# drive_brake.net
KiCad netlist of a schematic drawn in EAGLE
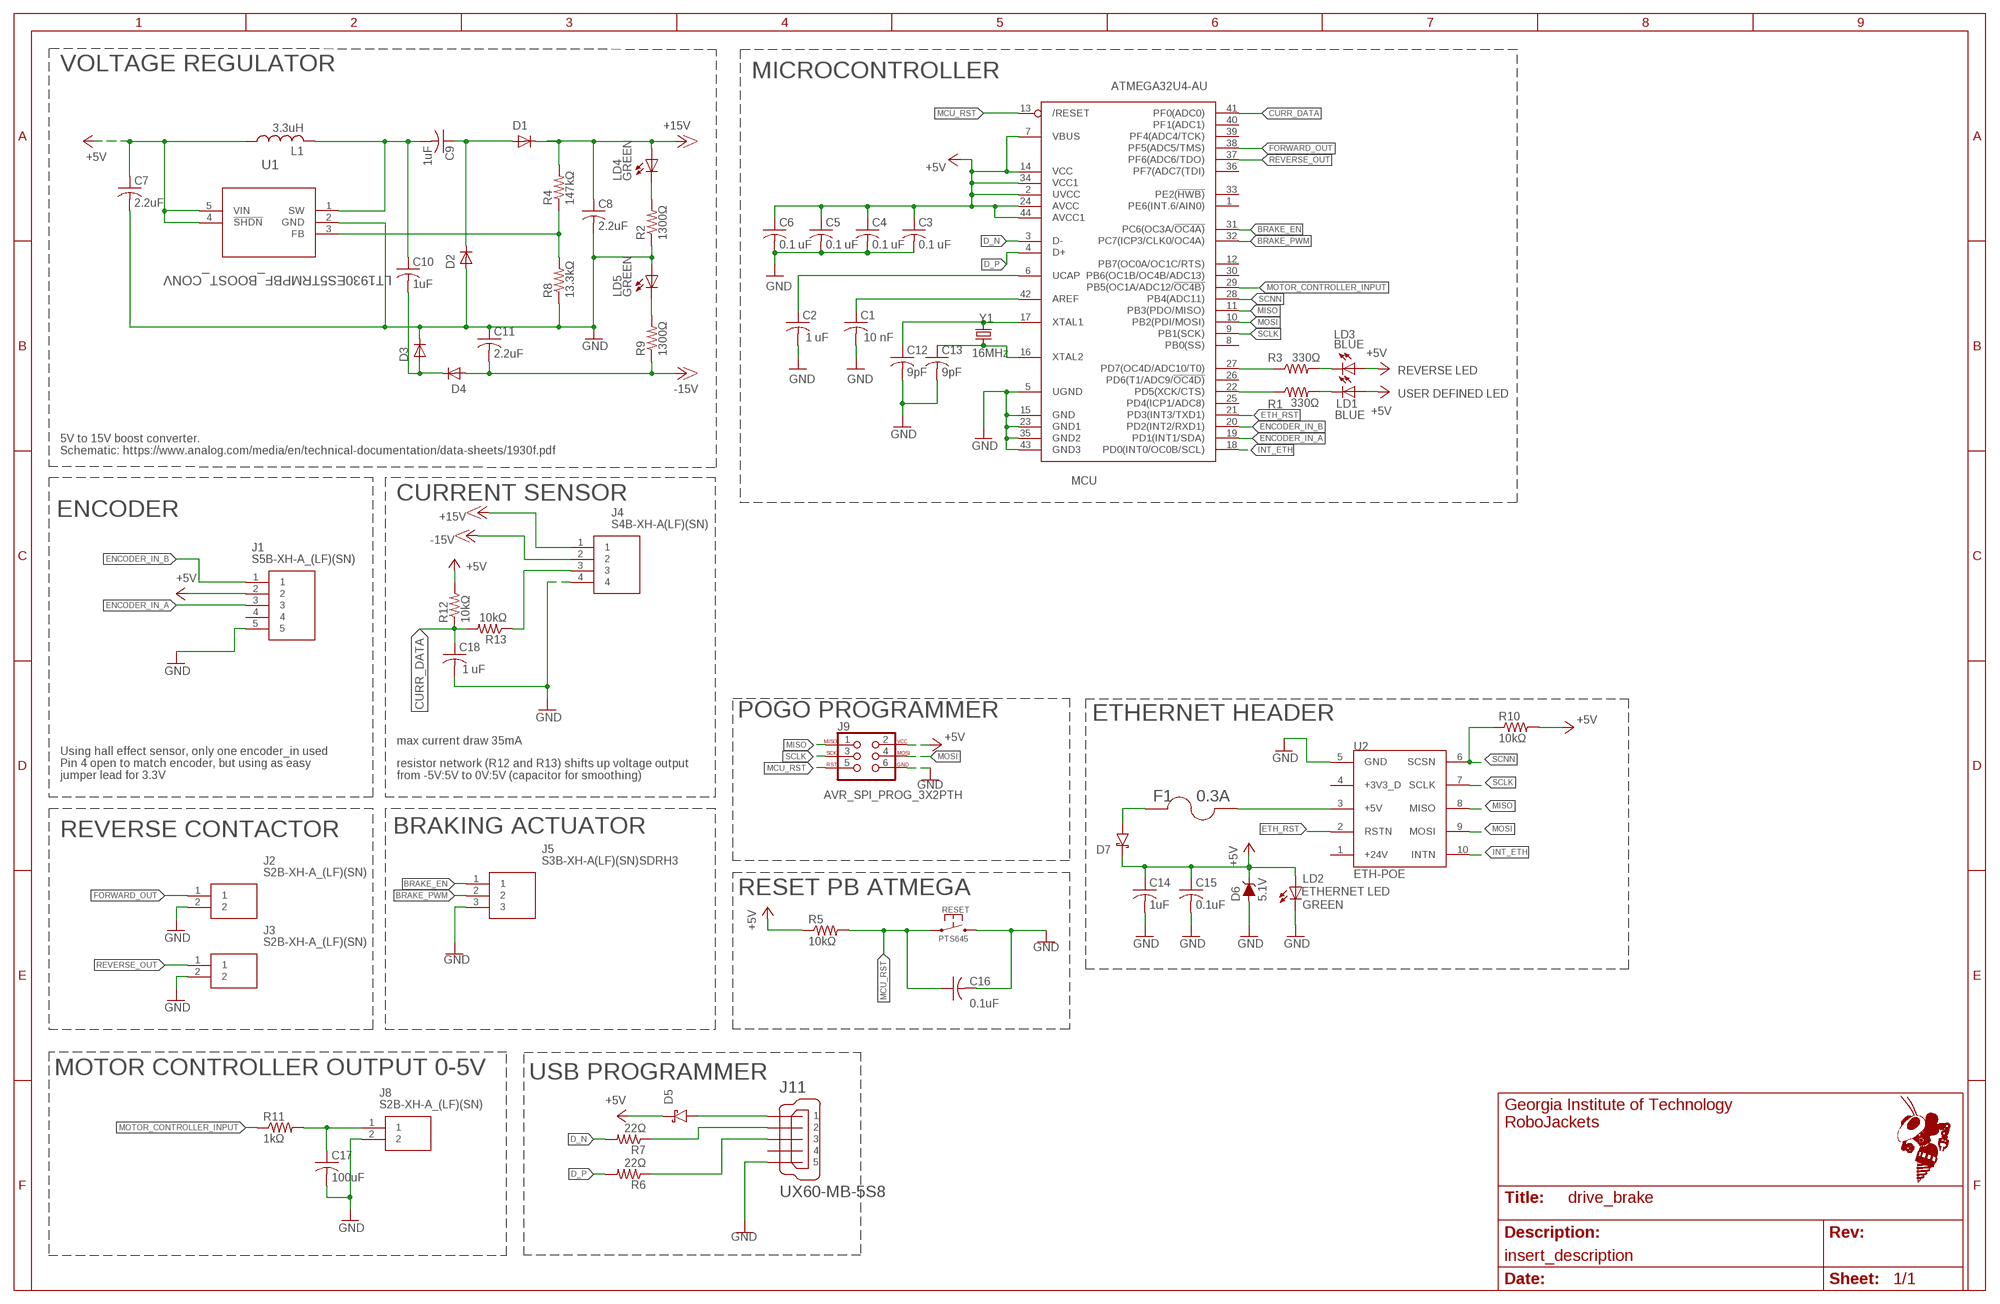
[diagram p0: schematic, sheet 1]

(export (version "E")
  (design (tool "Eeschema 10.0.6"))
  (components
    (comp (ref "C1")
      (value "10 nF")
      (footprint "eagle-import:C0603")
      (libsource (lib "eagle-import") (part "C-USC0603"))
    )
    (comp (ref "C2")
      (value "1 uF")
      (footprint "eagle-import:C0603")
      (libsource (lib "eagle-import") (part "C-USC0603"))
    )
    (comp (ref "C3")
      (value "0.1 uF")
      (footprint "eagle-import:C0603")
      (libsource (lib "eagle-import") (part "C-USC0603"))
    )
    (comp (ref "C4")
      (value "0.1 uF")
      (footprint "eagle-import:C0603")
      (libsource (lib "eagle-import") (part "C-USC0603"))
    )
    (comp (ref "C5")
      (value "0.1 uF")
      (footprint "eagle-import:C0603")
      (libsource (lib "eagle-import") (part "C-USC0603"))
    )
    (comp (ref "C6")
      (value "0.1 uF")
      (footprint "eagle-import:C0603")
      (libsource (lib "eagle-import") (part "C-USC0603"))
    )
    (comp (ref "C7")
      (value "2.2uF")
      (footprint "eagle-import:C0805")
      (libsource (lib "eagle-import") (part "C-USC0805"))
    )
    (comp (ref "C8")
      (value "2.2uF")
      (footprint "eagle-import:C1206")
      (libsource (lib "eagle-import") (part "C-USC1206"))
    )
    (comp (ref "C9")
      (value "1uF")
      (footprint "eagle-import:C0603")
      (libsource (lib "eagle-import") (part "C-USC0603"))
    )
    (comp (ref "C10")
      (value "1uF")
      (footprint "eagle-import:C0603")
      (libsource (lib "eagle-import") (part "C-USC0603"))
    )
    (comp (ref "C11")
      (value "2.2uF")
      (footprint "eagle-import:C1206")
      (libsource (lib "eagle-import") (part "C-USC1206"))
    )
    (comp (ref "C12")
      (value "9pF")
      (footprint "eagle-import:C0603")
      (libsource (lib "eagle-import") (part "C-USC0603"))
    )
    (comp (ref "C13")
      (value "9pF")
      (footprint "eagle-import:C0603")
      (libsource (lib "eagle-import") (part "C-USC0603"))
    )
    (comp (ref "C14")
      (value "1uF")
      (footprint "eagle-import:C0603")
      (libsource (lib "eagle-import") (part "C-USC0603"))
    )
    (comp (ref "C15")
      (value "0.1uF")
      (footprint "eagle-import:C0603")
      (libsource (lib "eagle-import") (part "C-USC0603"))
    )
    (comp (ref "C16")
      (value "0.1uF")
      (footprint "eagle-import:C0603")
      (libsource (lib "eagle-import") (part "C-USC0603"))
    )
    (comp (ref "C17")
      (value "100uF")
      (footprint "eagle-import:C1206")
      (libsource (lib "eagle-import") (part "C-USC1206"))
    )
    (comp (ref "C18")
      (value "1 uF")
      (footprint "eagle-import:C0603")
      (libsource (lib "eagle-import") (part "C-USC0603"))
    )
    (comp (ref "D1")
      (value "DIODE-SOD123")
      (footprint "eagle-import:SOD123")
      (libsource (lib "eagle-import") (part "DIODE-SOD123"))
    )
    (comp (ref "D2")
      (value "DIODE-SOD123")
      (footprint "eagle-import:SOD123")
      (libsource (lib "eagle-import") (part "DIODE-SOD123"))
    )
    (comp (ref "D3")
      (value "DIODE-SOD123")
      (footprint "eagle-import:SOD123")
      (libsource (lib "eagle-import") (part "DIODE-SOD123"))
    )
    (comp (ref "D4")
      (value "DIODE-SOD123")
      (footprint "eagle-import:SOD123")
      (libsource (lib "eagle-import") (part "DIODE-SOD123"))
    )
    (comp (ref "D5")
      (value "SCHOTTKYSOD-323")
      (footprint "eagle-import:SOD-323")
      (libsource (lib "eagle-import") (part "SCHOTTKYSOD-323"))
    )
    (comp (ref "D6")
      (value "5.1V")
      (footprint "eagle-import:SOD-323")
      (libsource (lib "eagle-import") (part "DIODE-ZENER-MM3Z3V3T1G"))
    )
    (comp (ref "D7")
      (value "SCHOTTKYSOD-323")
      (footprint "eagle-import:SOD-323")
      (libsource (lib "eagle-import") (part "SCHOTTKYSOD-323"))
    )
    (comp (ref "F1")
      (value "0.3A")
      (footprint "eagle-import:F1206")
      (libsource (lib "eagle-import") (part "FUSE1206"))
    )
    (comp (ref "J1")
      (value "S5B-XH-A_(LF)(SN)")
      (footprint "eagle-import:SHDR5W80P0X250_1X5_1490X1150X6")
      (fields
        (field (name "MANUFACTURER_PART_NUMBER") "S5B-XH-A (LF)(SN)")
        (field (name "RS_PART_NUMBER") "5469072")
      )
      (libsource (lib "eagle-import") (part "S5B-XH-A_(LF)(SN)"))
    )
    (comp (ref "J2")
      (value "S2B-XH-A_(LF)(SN)")
      (footprint "eagle-import:SHDR2W80P0X250_1X2_740X1150X61")
      (fields (field (name "MANUFACTURER_PART_NUMBER") "S2B-XH-A (LF)(SN)"))
      (libsource (lib "eagle-import") (part "S2B-XH-A_(LF)(SN)"))
    )
    (comp (ref "J3")
      (value "S2B-XH-A_(LF)(SN)")
      (footprint "eagle-import:SHDR2W80P0X250_1X2_740X1150X61")
      (fields (field (name "MANUFACTURER_PART_NUMBER") "S2B-XH-A (LF)(SN)"))
      (libsource (lib "eagle-import") (part "S2B-XH-A_(LF)(SN)"))
    )
    (comp (ref "J4")
      (value "S4B-XH-A(LF)(SN)")
      (footprint "eagle-import:SHDR4W64P0X250_1X4_1240X1155X7")
      (fields (field (name "RS_PART_NUMBER") "8201589P"))
      (libsource (lib "eagle-import") (part "S4B-XH-A(LF)(SN)"))
    )
    (comp (ref "J5")
      (value "S3B-XH-A(LF)(SN)SDRH3")
      (footprint "eagle-import:SHDR4")
      (libsource (lib "eagle-import") (part "S3B-XH-A(LF)(SN)SDRH3"))
    )
    (comp (ref "J8")
      (value "S2B-XH-A_(LF)(SN)")
      (footprint "eagle-import:SHDR2W80P0X250_1X2_740X1150X61")
      (fields (field (name "MANUFACTURER_PART_NUMBER") "S2B-XH-A (LF)(SN)"))
      (libsource (lib "eagle-import") (part "S2B-XH-A_(LF)(SN)"))
    )
    (comp (ref "J9")
      (value "AVR_SPI_PROG_3X2PTH")
      (footprint "eagle-import:2X3")
      (libsource (lib "eagle-import") (part "AVR_SPI_PROG_3X2PTH"))
    )
    (comp (ref "J11")
      (value "UX60-MB-5S8")
      (footprint "eagle-import:UX60-MB-5S8")
      (libsource (lib "eagle-import") (part "UX60-MB-5S?8"))
    )
    (comp (ref "L1")
      (value "3.3uH")
      (footprint "eagle-import:L3225M")
      (libsource (lib "eagle-import") (part "L-USL3225M"))
    )
    (comp (ref "LD1")
      (value "BLUE")
      (footprint "eagle-import:LED-0603")
      (libsource (lib "eagle-import") (part "LED0603"))
    )
    (comp (ref "LD2")
      (value "GREEN")
      (footprint "eagle-import:LED-0603")
      (libsource (lib "eagle-import") (part "LED0603"))
    )
    (comp (ref "LD3")
      (value "BLUE")
      (footprint "eagle-import:LED-0603")
      (libsource (lib "eagle-import") (part "LED0603"))
    )
    (comp (ref "LD4")
      (value "GREEN")
      (footprint "eagle-import:LED-0603")
      (libsource (lib "eagle-import") (part "LED0603"))
    )
    (comp (ref "LD5")
      (value "GREEN")
      (footprint "eagle-import:LED-0603")
      (libsource (lib "eagle-import") (part "LED0603"))
    )
    (comp (ref "MCU")
      (value "ATMEGA32U4-AU")
      (footprint "eagle-import:TQFP44")
      (libsource (lib "eagle-import") (part "ATMEGA32U4-AU"))
    )
    (comp (ref "R1")
      (value "330Ω")
      (footprint "eagle-import:0603-RES")
      (libsource (lib "eagle-import") (part "RESISTOR0603-RES"))
    )
    (comp (ref "R2")
      (value "1300Ω")
      (footprint "eagle-import:R0603")
      (libsource (lib "eagle-import") (part "R-US_R0603"))
    )
    (comp (ref "R3")
      (value "330Ω")
      (footprint "eagle-import:0603-RES")
      (libsource (lib "eagle-import") (part "RESISTOR0603-RES"))
    )
    (comp (ref "R4")
      (value "147kΩ")
      (footprint "eagle-import:R0603")
      (libsource (lib "eagle-import") (part "R-US_R0603"))
    )
    (comp (ref "R5")
      (value "10kΩ")
      (footprint "eagle-import:R0603")
      (libsource (lib "eagle-import") (part "R-US_R0603"))
    )
    (comp (ref "R6")
      (value "22Ω")
      (footprint "eagle-import:0603-RES")
      (libsource (lib "eagle-import") (part "RESISTOR0603-RES"))
    )
    (comp (ref "R7")
      (value "22Ω")
      (footprint "eagle-import:0603-RES")
      (libsource (lib "eagle-import") (part "RESISTOR0603-RES"))
    )
    (comp (ref "R8")
      (value "13.3kΩ")
      (footprint "eagle-import:R0603")
      (libsource (lib "eagle-import") (part "R-US_R0603"))
    )
    (comp (ref "R9")
      (value "1300Ω")
      (footprint "eagle-import:R0603")
      (libsource (lib "eagle-import") (part "R-US_R0603"))
    )
    (comp (ref "R10")
      (value "10kΩ")
      (footprint "eagle-import:R0603")
      (libsource (lib "eagle-import") (part "R-US_R0603"))
    )
    (comp (ref "R11")
      (value "1kΩ")
      (footprint "eagle-import:0603-RES")
      (libsource (lib "eagle-import") (part "RESISTOR0603-RES"))
    )
    (comp (ref "R12")
      (value "10kΩ")
      (footprint "eagle-import:0603-RES")
      (libsource (lib "eagle-import") (part "RESISTOR0603-RES"))
    )
    (comp (ref "R13")
      (value "10kΩ")
      (footprint "eagle-import:0603-RES")
      (libsource (lib "eagle-import") (part "RESISTOR0603-RES"))
    )
    (comp (ref "RESET")
      (value "PTS645")
      (footprint "eagle-import:PTS645")
      (libsource (lib "eagle-import") (part "PTS645"))
    )
    (comp (ref "U1")
      (value "LT1930ES5TRMPBF_BOOST_CONV")
      (footprint "eagle-import:SOT-5_S")
      (fields (field (name "MANUFACTURER_PART_NUMBER") "LT1930ES5#TRMPBF"))
      (libsource (lib "eagle-import") (part "LT1930ES5TRMPBF_BOOST_CONV"))
    )
    (comp (ref "U2")
      (value "ETH-POE")
      (footprint "eagle-import:HDRVR10W64P4000X254_2X5_1016X508X254B")
      (libsource (lib "eagle-import") (part "ETH-POE"))
    )
    (comp (ref "Y1")
      (value "16MHz")
      (footprint "eagle-import:CRYSTAL-SMD-5X3")
      (libsource (lib "eagle-import") (part "CRYSTAL5X3"))
    )
  )
  (nets
    (net (code "1") (name "+5V") (class "Default")
      (node (ref "C14") (pin "1") (pinfunction "1_1") (pintype "passive"))
      (node (ref "C15") (pin "1") (pinfunction "1_1") (pintype "passive"))
      (node (ref "C3") (pin "1") (pinfunction "1_1") (pintype "passive"))
      (node (ref "C4") (pin "1") (pinfunction "1_1") (pintype "passive"))
      (node (ref "C5") (pin "1") (pinfunction "1_1") (pintype "passive"))
      (node (ref "C6") (pin "1") (pinfunction "1_1") (pintype "passive"))
      (node (ref "C7") (pin "1") (pinfunction "1_1") (pintype "passive"))
      (node (ref "D5") (pin "C") (pinfunction "C_C") (pintype "passive"))
      (node (ref "D6") (pin "C") (pinfunction "C_C") (pintype "passive"))
      (node (ref "D7") (pin "C") (pinfunction "C_C") (pintype "passive"))
      (node (ref "J1") (pin "2") (pinfunction "2_2") (pintype "bidirectional"))
      (node (ref "J9") (pin "2") (pinfunction "2_2") (pintype "passive"))
      (node (ref "L1") (pin "1") (pinfunction "1_1") (pintype "passive"))
      (node (ref "LD1") (pin "A") (pinfunction "A_A") (pintype "passive"))
      (node (ref "LD2") (pin "A") (pinfunction "A_A") (pintype "passive"))
      (node (ref "LD3") (pin "A") (pinfunction "A_A") (pintype "passive"))
      (node (ref "MCU") (pin "14") (pinfunction "VCC_14") (pintype "bidirectional"))
      (node (ref "MCU") (pin "2") (pinfunction "UVCC_2") (pintype "bidirectional"))
      (node (ref "MCU") (pin "24") (pinfunction "AVCC_24") (pintype "bidirectional"))
      (node (ref "MCU") (pin "34") (pinfunction "VCC1_34") (pintype "bidirectional"))
      (node (ref "MCU") (pin "44") (pinfunction "AVCC1_44") (pintype "bidirectional"))
      (node (ref "MCU") (pin "7") (pinfunction "VBUS_7") (pintype "bidirectional"))
      (node (ref "R10") (pin "2") (pinfunction "2_2") (pintype "passive"))
      (node (ref "R12") (pin "2") (pinfunction "2_2") (pintype "passive"))
      (node (ref "R5") (pin "1") (pinfunction "1_1") (pintype "passive"))
      (node (ref "U1") (pin "4") (pinfunction "~{SHDN}_4") (pintype "input"))
      (node (ref "U1") (pin "5") (pinfunction "VIN_5") (pintype "power_in"))
    )
    (net (code "2") (name "+15V") (class "Default")
      (node (ref "C8") (pin "1") (pinfunction "1_1") (pintype "passive"))
      (node (ref "D1") (pin "C") (pinfunction "C_C") (pintype "passive"))
      (node (ref "J4") (pin "1") (pinfunction "1_1") (pintype "bidirectional"))
      (node (ref "LD4") (pin "A") (pinfunction "A_A") (pintype "passive"))
      (node (ref "R4") (pin "2") (pinfunction "2_2") (pintype "passive"))
    )
    (net (code "3") (name "-15V") (class "Default")
      (node (ref "C11") (pin "2") (pinfunction "2_2") (pintype "passive"))
      (node (ref "D4") (pin "A") (pinfunction "A_A") (pintype "passive"))
      (node (ref "J4") (pin "2") (pinfunction "2_2") (pintype "bidirectional"))
      (node (ref "R9") (pin "1") (pinfunction "1_1") (pintype "passive"))
    )
    (net (code "4") (name "BRAKE_EN") (class "Default")
      (node (ref "J5") (pin "1") (pinfunction "1_1") (pintype "bidirectional"))
      (node (ref "MCU") (pin "31") (pinfunction "PC6(OC3A/~{OC4A})_31") (pintype "bidirectional"))
    )
    (net (code "5") (name "BRAKE_PWM") (class "Default")
      (node (ref "J5") (pin "2") (pinfunction "2_2") (pintype "bidirectional"))
      (node (ref "MCU") (pin "32") (pinfunction "PC7(ICP3/CLK0/OC4A)_32") (pintype "bidirectional"))
    )
    (net (code "6") (name "CURR_DATA") (class "Default")
      (node (ref "C18") (pin "1") (pinfunction "1_1") (pintype "passive"))
      (node (ref "MCU") (pin "41") (pinfunction "PF0(ADC0)_41") (pintype "bidirectional"))
      (node (ref "R12") (pin "1") (pinfunction "1_1") (pintype "passive"))
      (node (ref "R13") (pin "2") (pinfunction "2_2") (pintype "passive"))
    )
    (net (code "7") (name "D_N") (class "Default")
      (node (ref "MCU") (pin "3") (pinfunction "D-_3") (pintype "bidirectional"))
      (node (ref "R7") (pin "2") (pinfunction "2_2") (pintype "passive"))
    )
    (net (code "8") (name "D_P") (class "Default")
      (node (ref "MCU") (pin "4") (pinfunction "D+_4") (pintype "bidirectional"))
      (node (ref "R6") (pin "2") (pinfunction "2_2") (pintype "passive"))
    )
    (net (code "9") (name "ENCODER_IN_A") (class "Default")
      (node (ref "J1") (pin "3") (pinfunction "3_3") (pintype "bidirectional"))
      (node (ref "MCU") (pin "19") (pinfunction "PD1(INT1/SDA)_19") (pintype "bidirectional"))
    )
    (net (code "10") (name "ENCODER_IN_B") (class "Default")
      (node (ref "J1") (pin "1") (pinfunction "1_1") (pintype "bidirectional"))
      (node (ref "MCU") (pin "20") (pinfunction "PD2(INT2/RXD1)_20") (pintype "bidirectional"))
    )
    (net (code "11") (name "ETH_RST") (class "Default")
      (node (ref "MCU") (pin "21") (pinfunction "PD3(INT3/TXD1)_21") (pintype "bidirectional"))
      (node (ref "U2") (pin "2") (pinfunction "RSTN_2") (pintype "bidirectional"))
    )
    (net (code "12") (name "FORWARD_OUT") (class "Default")
      (node (ref "J2") (pin "1") (pinfunction "1_1") (pintype "bidirectional"))
      (node (ref "MCU") (pin "38") (pinfunction "PF5(ADC5/TMS)_38") (pintype "bidirectional"))
    )
    (net (code "13") (name "GND") (class "Default")
      (node (ref "C1") (pin "2") (pinfunction "2_2") (pintype "passive"))
      (node (ref "C11") (pin "1") (pinfunction "1_1") (pintype "passive"))
      (node (ref "C12") (pin "2") (pinfunction "2_2") (pintype "passive"))
      (node (ref "C13") (pin "2") (pinfunction "2_2") (pintype "passive"))
      (node (ref "C14") (pin "2") (pinfunction "2_2") (pintype "passive"))
      (node (ref "C15") (pin "2") (pinfunction "2_2") (pintype "passive"))
      (node (ref "C16") (pin "2") (pinfunction "2_2") (pintype "passive"))
      (node (ref "C17") (pin "2") (pinfunction "2_2") (pintype "passive"))
      (node (ref "C18") (pin "2") (pinfunction "2_2") (pintype "passive"))
      (node (ref "C2") (pin "2") (pinfunction "2_2") (pintype "passive"))
      (node (ref "C3") (pin "2") (pinfunction "2_2") (pintype "passive"))
      (node (ref "C4") (pin "2") (pinfunction "2_2") (pintype "passive"))
      (node (ref "C5") (pin "2") (pinfunction "2_2") (pintype "passive"))
      (node (ref "C6") (pin "2") (pinfunction "2_2") (pintype "passive"))
      (node (ref "C7") (pin "2") (pinfunction "2_2") (pintype "passive"))
      (node (ref "C8") (pin "2") (pinfunction "2_2") (pintype "passive"))
      (node (ref "D2") (pin "A") (pinfunction "A_A") (pintype "passive"))
      (node (ref "D3") (pin "C") (pinfunction "C_C") (pintype "passive"))
      (node (ref "D6") (pin "A") (pinfunction "A_A") (pintype "passive"))
      (node (ref "J1") (pin "5") (pinfunction "5_5") (pintype "bidirectional"))
      (node (ref "J11") (pin "5") (pinfunction "5_5") (pintype "passive"))
      (node (ref "J2") (pin "2") (pinfunction "2_2") (pintype "bidirectional"))
      (node (ref "J3") (pin "2") (pinfunction "2_2") (pintype "bidirectional"))
      (node (ref "J4") (pin "4") (pinfunction "4_4") (pintype "bidirectional"))
      (node (ref "J5") (pin "3") (pinfunction "3_3") (pintype "bidirectional"))
      (node (ref "J8") (pin "2") (pinfunction "2_2") (pintype "bidirectional"))
      (node (ref "J9") (pin "6") (pinfunction "6_6") (pintype "passive"))
      (node (ref "LD2") (pin "C") (pinfunction "C_C") (pintype "passive"))
      (node (ref "LD5") (pin "A") (pinfunction "A_A") (pintype "passive"))
      (node (ref "MCU") (pin "15") (pinfunction "GND_15") (pintype "bidirectional"))
      (node (ref "MCU") (pin "23") (pinfunction "GND1_23") (pintype "bidirectional"))
      (node (ref "MCU") (pin "35") (pinfunction "GND2_35") (pintype "bidirectional"))
      (node (ref "MCU") (pin "43") (pinfunction "GND3_43") (pintype "bidirectional"))
      (node (ref "MCU") (pin "5") (pinfunction "UGND_5") (pintype "bidirectional"))
      (node (ref "R2") (pin "1") (pinfunction "1_1") (pintype "passive"))
      (node (ref "R8") (pin "1") (pinfunction "1_1") (pintype "passive"))
      (node (ref "RESET") (pin "P$3") (pinfunction "2_P$3") (pintype "passive"))
      (node (ref "RESET") (pin "P$4") (pinfunction "2_P$4") (pintype "passive"))
      (node (ref "U1") (pin "2") (pinfunction "GND_2") (pintype "power_in"))
      (node (ref "U2") (pin "5") (pinfunction "GND_5") (pintype "bidirectional"))
    )
    (net (code "14") (name "INT_ETH") (class "Default")
      (node (ref "MCU") (pin "18") (pinfunction "PD0(INT0/OC0B/SCL)_18") (pintype "bidirectional"))
      (node (ref "U2") (pin "10") (pinfunction "INTN_10") (pintype "bidirectional"))
    )
    (net (code "15") (name "MCU_RST") (class "Default")
      (node (ref "C16") (pin "1") (pinfunction "1_1") (pintype "passive"))
      (node (ref "J9") (pin "5") (pinfunction "5_5") (pintype "passive"))
      (node (ref "MCU") (pin "13") (pinfunction "/RESET_13") (pintype "bidirectional"))
      (node (ref "R5") (pin "2") (pinfunction "2_2") (pintype "passive"))
      (node (ref "RESET") (pin "P$1") (pinfunction "1_P$1") (pintype "passive"))
      (node (ref "RESET") (pin "P$2") (pinfunction "1_P$2") (pintype "passive"))
    )
    (net (code "16") (name "MISO") (class "Default")
      (node (ref "J9") (pin "1") (pinfunction "1_1") (pintype "passive"))
      (node (ref "MCU") (pin "11") (pinfunction "PB3(PDO/MISO)_11") (pintype "bidirectional"))
      (node (ref "U2") (pin "8") (pinfunction "MISO_8") (pintype "bidirectional"))
    )
    (net (code "17") (name "MOSI") (class "Default")
      (node (ref "J9") (pin "4") (pinfunction "4_4") (pintype "passive"))
      (node (ref "MCU") (pin "10") (pinfunction "PB2(PDI/MOSI)_10") (pintype "bidirectional"))
      (node (ref "U2") (pin "9") (pinfunction "MOSI_9") (pintype "bidirectional"))
    )
    (net (code "18") (name "MOTOR_CONTROLLER_INPUT") (class "Default")
      (node (ref "MCU") (pin "29") (pinfunction "PB5(OC1A/ADC12/~{OC4B})_29") (pintype "bidirectional"))
      (node (ref "R11") (pin "1") (pinfunction "1_1") (pintype "passive"))
    )
    (net (code "19") (name "Net-(C9-Pad1)") (class "Default")
      (node (ref "C9") (pin "1") (pinfunction "1_1") (pintype "passive"))
      (node (ref "D1") (pin "A") (pinfunction "A_A") (pintype "passive"))
      (node (ref "D2") (pin "C") (pinfunction "C_C") (pintype "passive"))
    )
    (net (code "20") (name "Net-(C10-Pad2)") (class "Default")
      (node (ref "C10") (pin "2") (pinfunction "2_2") (pintype "passive"))
      (node (ref "D3") (pin "A") (pinfunction "A_A") (pintype "passive"))
      (node (ref "D4") (pin "C") (pinfunction "C_C") (pintype "passive"))
    )
    (net (code "21") (name "Net-(C17-Pad1)") (class "Default")
      (node (ref "C17") (pin "1") (pinfunction "1_1") (pintype "passive"))
      (node (ref "J8") (pin "1") (pinfunction "1_1") (pintype "bidirectional"))
      (node (ref "R11") (pin "2") (pinfunction "2_2") (pintype "passive"))
    )
    (net (code "22") (name "Net-(D5-PadA)") (class "Default")
      (node (ref "D5") (pin "A") (pinfunction "A_A") (pintype "passive"))
      (node (ref "J11") (pin "1") (pinfunction "1_1") (pintype "passive"))
    )
    (net (code "23") (name "Net-(D7-PadA)") (class "Default")
      (node (ref "D7") (pin "A") (pinfunction "A_A") (pintype "passive"))
      (node (ref "F1") (pin "1") (pinfunction "1_1") (pintype "passive"))
    )
    (net (code "24") (name "Net-(J4-Pad3)") (class "Default")
      (node (ref "J4") (pin "3") (pinfunction "3_3") (pintype "bidirectional"))
      (node (ref "R13") (pin "1") (pinfunction "1_1") (pintype "passive"))
    )
    (net (code "25") (name "Net-(J11-Pad2)") (class "Default")
      (node (ref "J11") (pin "2") (pinfunction "2_2") (pintype "passive"))
      (node (ref "R7") (pin "1") (pinfunction "1_1") (pintype "passive"))
    )
    (net (code "26") (name "Net-(J11-Pad3)") (class "Default")
      (node (ref "J11") (pin "3") (pinfunction "3_3") (pintype "passive"))
      (node (ref "R6") (pin "1") (pinfunction "1_1") (pintype "passive"))
    )
    (net (code "27") (name "Net-(LD1-PadC)") (class "Default")
      (node (ref "LD1") (pin "C") (pinfunction "C_C") (pintype "passive"))
      (node (ref "R1") (pin "2") (pinfunction "2_2") (pintype "passive"))
    )
    (net (code "28") (name "Net-(LD3-PadC)") (class "Default")
      (node (ref "LD3") (pin "C") (pinfunction "C_C") (pintype "passive"))
      (node (ref "R3") (pin "2") (pinfunction "2_2") (pintype "passive"))
    )
    (net (code "29") (name "Net-(LD4-PadC)") (class "Default")
      (node (ref "LD4") (pin "C") (pinfunction "C_C") (pintype "passive"))
      (node (ref "R2") (pin "2") (pinfunction "2_2") (pintype "passive"))
    )
    (net (code "30") (name "Net-(LD5-PadC)") (class "Default")
      (node (ref "LD5") (pin "C") (pinfunction "C_C") (pintype "passive"))
      (node (ref "R9") (pin "2") (pinfunction "2_2") (pintype "passive"))
    )
    (net (code "31") (name "Net-(MCU-AREF)") (class "Default")
      (node (ref "C1") (pin "1") (pinfunction "1_1") (pintype "passive"))
      (node (ref "MCU") (pin "42") (pinfunction "AREF_42") (pintype "bidirectional"))
    )
    (net (code "32") (name "Net-(MCU-PD5(XCK{slash}CTS))") (class "Default")
      (node (ref "MCU") (pin "22") (pinfunction "PD5(XCK/CTS)_22") (pintype "bidirectional"))
      (node (ref "R1") (pin "1") (pinfunction "1_1") (pintype "passive"))
    )
    (net (code "33") (name "Net-(MCU-PD7(OC4D{slash}ADC10{slash}T0))") (class "Default")
      (node (ref "MCU") (pin "27") (pinfunction "PD7(OC4D/ADC10/T0)_27") (pintype "bidirectional"))
      (node (ref "R3") (pin "1") (pinfunction "1_1") (pintype "passive"))
    )
    (net (code "34") (name "Net-(MCU-UCAP)") (class "Default")
      (node (ref "C2") (pin "1") (pinfunction "1_1") (pintype "passive"))
      (node (ref "MCU") (pin "6") (pinfunction "UCAP_6") (pintype "bidirectional"))
    )
    (net (code "35") (name "Net-(MCU-XTAL1)") (class "Default")
      (node (ref "C12") (pin "1") (pinfunction "1_1") (pintype "passive"))
      (node (ref "MCU") (pin "17") (pinfunction "XTAL1_17") (pintype "bidirectional"))
      (node (ref "Y1") (pin "3") (pinfunction "2_3") (pintype "passive"))
    )
    (net (code "36") (name "Net-(MCU-XTAL2)") (class "Default")
      (node (ref "C13") (pin "1") (pinfunction "1_1") (pintype "passive"))
      (node (ref "MCU") (pin "16") (pinfunction "XTAL2_16") (pintype "bidirectional"))
      (node (ref "Y1") (pin "1") (pinfunction "1_1") (pintype "passive"))
    )
    (net (code "37") (name "Net-(U1-FB)") (class "Default")
      (node (ref "R4") (pin "1") (pinfunction "1_1") (pintype "passive"))
      (node (ref "R8") (pin "2") (pinfunction "2_2") (pintype "passive"))
      (node (ref "U1") (pin "3") (pinfunction "FB_3") (pintype "input"))
    )
    (net (code "38") (name "Net-(U1-SW)") (class "Default")
      (node (ref "C10") (pin "1") (pinfunction "1_1") (pintype "passive"))
      (node (ref "C9") (pin "2") (pinfunction "2_2") (pintype "passive"))
      (node (ref "L1") (pin "2") (pinfunction "2_2") (pintype "passive"))
      (node (ref "U1") (pin "1") (pinfunction "SW_1") (pintype "passive"))
    )
    (net (code "39") (name "Net-(U2-+5V)") (class "Default")
      (node (ref "F1") (pin "2") (pinfunction "2_2") (pintype "passive"))
      (node (ref "U2") (pin "3") (pinfunction "+5V_3") (pintype "bidirectional"))
    )
    (net (code "40") (name "REVERSE_OUT") (class "Default")
      (node (ref "J3") (pin "1") (pinfunction "1_1") (pintype "bidirectional"))
      (node (ref "MCU") (pin "37") (pinfunction "PF6(ADC6/TDO)_37") (pintype "bidirectional"))
    )
    (net (code "41") (name "SCLK") (class "Default")
      (node (ref "J9") (pin "3") (pinfunction "3_3") (pintype "passive"))
      (node (ref "MCU") (pin "9") (pinfunction "PB1(SCK)_9") (pintype "bidirectional"))
      (node (ref "U2") (pin "7") (pinfunction "SCLK_7") (pintype "bidirectional"))
    )
    (net (code "42") (name "SCNN") (class "Default")
      (node (ref "MCU") (pin "28") (pinfunction "PB4(ADC11)_28") (pintype "bidirectional"))
      (node (ref "R10") (pin "1") (pinfunction "1_1") (pintype "passive"))
      (node (ref "U2") (pin "6") (pinfunction "SCSN_6") (pintype "bidirectional"))
    )
    (net (code "43") (name "unconnected-(J1-Pad4)") (class "Default")
      (node (ref "J1") (pin "4") (pinfunction "4_4") (pintype "bidirectional"))
    )
    (net (code "44") (name "unconnected-(J11-Pad4)") (class "Default")
      (node (ref "J11") (pin "4") (pinfunction "4_4") (pintype "passive"))
    )
    (net (code "45") (name "unconnected-(MCU-PB0(SS)-Pad8)") (class "Default")
      (node (ref "MCU") (pin "8") (pinfunction "PB0(SS)_8") (pintype "bidirectional"))
    )
    (net (code "46") (name "unconnected-(MCU-PB6(OC1B{slash}OC4B{slash}ADC13)-Pad30)") (class "Default")
      (node (ref "MCU") (pin "30") (pinfunction "PB6(OC1B/OC4B/ADC13)_30") (pintype "bidirectional"))
    )
    (net (code "47") (name "unconnected-(MCU-PB7(OC0A{slash}OC1C{slash}RTS)-Pad12)") (class "Default")
      (node (ref "MCU") (pin "12") (pinfunction "PB7(OC0A/OC1C/RTS)_12") (pintype "bidirectional"))
    )
    (net (code "48") (name "unconnected-(MCU-PD4(ICP1{slash}ADC8)-Pad25)") (class "Default")
      (node (ref "MCU") (pin "25") (pinfunction "PD4(ICP1/ADC8)_25") (pintype "bidirectional"))
    )
    (net (code "49") (name "unconnected-(MCU-PD6(T1{slash}ADC9{slash}~{OC4D})-Pad26)") (class "Default")
      (node (ref "MCU") (pin "26") (pinfunction "PD6(T1/ADC9/~{OC4D})_26") (pintype "bidirectional"))
    )
    (net (code "50") (name "unconnected-(MCU-PE2(~{HWB})-Pad33)") (class "Default")
      (node (ref "MCU") (pin "33") (pinfunction "PE2(~{HWB})_33") (pintype "bidirectional"))
    )
    (net (code "51") (name "unconnected-(MCU-PE6(INT.6{slash}AIN0)-Pad1)") (class "Default")
      (node (ref "MCU") (pin "1") (pinfunction "PE6(INT.6/AIN0)_1") (pintype "bidirectional"))
    )
    (net (code "52") (name "unconnected-(MCU-PF1(ADC1)-Pad40)") (class "Default")
      (node (ref "MCU") (pin "40") (pinfunction "PF1(ADC1)_40") (pintype "bidirectional"))
    )
    (net (code "53") (name "unconnected-(MCU-PF4(ADC4{slash}TCK)-Pad39)") (class "Default")
      (node (ref "MCU") (pin "39") (pinfunction "PF4(ADC4/TCK)_39") (pintype "bidirectional"))
    )
    (net (code "54") (name "unconnected-(MCU-PF7(ADC7(TDI)-Pad36)") (class "Default")
      (node (ref "MCU") (pin "36") (pinfunction "PF7(ADC7(TDI)_36") (pintype "bidirectional"))
    )
    (net (code "55") (name "unconnected-(U2-+3V3_D-Pad4)") (class "Default")
      (node (ref "U2") (pin "4") (pinfunction "+3V3_D_4") (pintype "bidirectional"))
    )
    (net (code "56") (name "unconnected-(U2-+24V-Pad1)") (class "Default")
      (node (ref "U2") (pin "1") (pinfunction "+24V_1") (pintype "bidirectional"))
    )
  )
)
